# SD_Card.net
KiCad netlist of a schematic drawn in Altium Designer
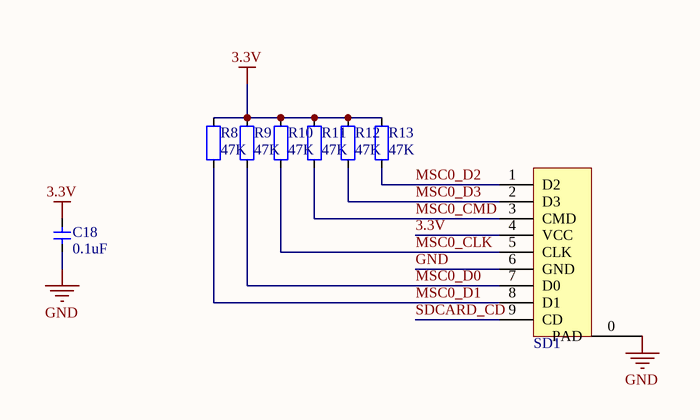
[diagram p0: SD_Card.SchDoc]

(export (version "E")
  (design (tool "Eeschema 10.0.6"))
  (components
    (comp (ref "C18")
      (value "0.1uF")
      (footprint "PCB_PassiveCap:CAP_0402")
      (description "Capacitor")
      (fields (field (name "Comment") "Cap_0402"))
      (libsource (lib "SCH_Passive") (part "Cap_0402"))
    )
    (comp (ref "R8")
      (value "47K")
      (footprint "PCB_PassiveRes:RES_0402")
      (description "Resistor")
      (fields (field (name "Comment") "Res_0402"))
      (libsource (lib "SCH_Passive") (part "Res_0402"))
    )
    (comp (ref "R9")
      (value "47K")
      (footprint "PCB_PassiveRes:RES_0402")
      (description "Resistor")
      (fields (field (name "Comment") "Res_0402"))
      (libsource (lib "SCH_Passive") (part "Res_0402"))
    )
    (comp (ref "R10")
      (value "47K")
      (footprint "PCB_PassiveRes:RES_0402")
      (description "Resistor")
      (fields (field (name "Comment") "Res_0402"))
      (libsource (lib "SCH_Passive") (part "Res_0402"))
    )
    (comp (ref "R11")
      (value "47K")
      (footprint "PCB_PassiveRes:RES_0402")
      (description "Resistor")
      (fields (field (name "Comment") "Res_0402"))
      (libsource (lib "SCH_Passive") (part "Res_0402"))
    )
    (comp (ref "R12")
      (value "47K")
      (footprint "PCB_PassiveRes:RES_0402")
      (description "Resistor")
      (fields (field (name "Comment") "Res_0402"))
      (libsource (lib "SCH_Passive") (part "Res_0402"))
    )
    (comp (ref "R13")
      (value "47K")
      (footprint "PCB_PassiveRes:RES_0402")
      (description "Resistor")
      (fields (field (name "Comment") "Res_0402"))
      (libsource (lib "SCH_Passive") (part "Res_0402"))
    )
    (comp (ref "SD1")
      (value "SD_Card_TF")
      (footprint "PCB_SDCard:SD_Card_TF")
      (description "SD")
      (libsource (lib "SCH_SDCard") (part "SD_Card_TF"))
    )
  )
  (nets
    (net (code "1") (name "/MSC0_CLK") (class "Default")
      (node (ref "R10") (pin "1") (pinfunction "1_1") (pintype "passive"))
      (node (ref "SD1") (pin "5") (pinfunction "CLK_5") (pintype "passive"))
    )
    (net (code "2") (name "/MSC0_CMD") (class "Default")
      (node (ref "R11") (pin "1") (pinfunction "1_1") (pintype "passive"))
      (node (ref "SD1") (pin "3") (pinfunction "CMD_3") (pintype "passive"))
    )
    (net (code "3") (name "/MSC0_D0") (class "Default")
      (node (ref "R9") (pin "1") (pinfunction "1_1") (pintype "passive"))
      (node (ref "SD1") (pin "7") (pinfunction "D0_7") (pintype "passive"))
    )
    (net (code "4") (name "/MSC0_D1") (class "Default")
      (node (ref "R8") (pin "1") (pinfunction "1_1") (pintype "passive"))
      (node (ref "SD1") (pin "8") (pinfunction "D1_8") (pintype "passive"))
    )
    (net (code "5") (name "/MSC0_D2") (class "Default")
      (node (ref "R13") (pin "1") (pinfunction "1_1") (pintype "passive"))
      (node (ref "SD1") (pin "1") (pinfunction "D2_1") (pintype "passive"))
    )
    (net (code "6") (name "/MSC0_D3") (class "Default")
      (node (ref "R12") (pin "1") (pinfunction "1_1") (pintype "passive"))
      (node (ref "SD1") (pin "2") (pinfunction "D3_2") (pintype "passive"))
    )
    (net (code "7") (name "/SDCARD_CD") (class "Default")
      (node (ref "SD1") (pin "9") (pinfunction "CD_9") (pintype "passive"))
    )
    (net (code "8") (name "3.3V") (class "Default")
      (node (ref "C18") (pin "2") (pinfunction "2_2") (pintype "passive"))
      (node (ref "R10") (pin "2") (pinfunction "2_2") (pintype "passive"))
      (node (ref "R11") (pin "2") (pinfunction "2_2") (pintype "passive"))
      (node (ref "R12") (pin "2") (pinfunction "2_2") (pintype "passive"))
      (node (ref "R13") (pin "2") (pinfunction "2_2") (pintype "passive"))
      (node (ref "R8") (pin "2") (pinfunction "2_2") (pintype "passive"))
      (node (ref "R9") (pin "2") (pinfunction "2_2") (pintype "passive"))
      (node (ref "SD1") (pin "4") (pinfunction "VCC_4") (pintype "passive"))
    )
    (net (code "9") (name "GND") (class "Default")
      (node (ref "C18") (pin "1") (pinfunction "1_1") (pintype "passive"))
      (node (ref "SD1") (pin "0") (pinfunction "PAD_0") (pintype "passive"))
      (node (ref "SD1") (pin "6") (pinfunction "GND_6") (pintype "passive"))
    )
  )
)
